# BreakoutBoard.net
KiCad netlist of a schematic drawn in EAGLE
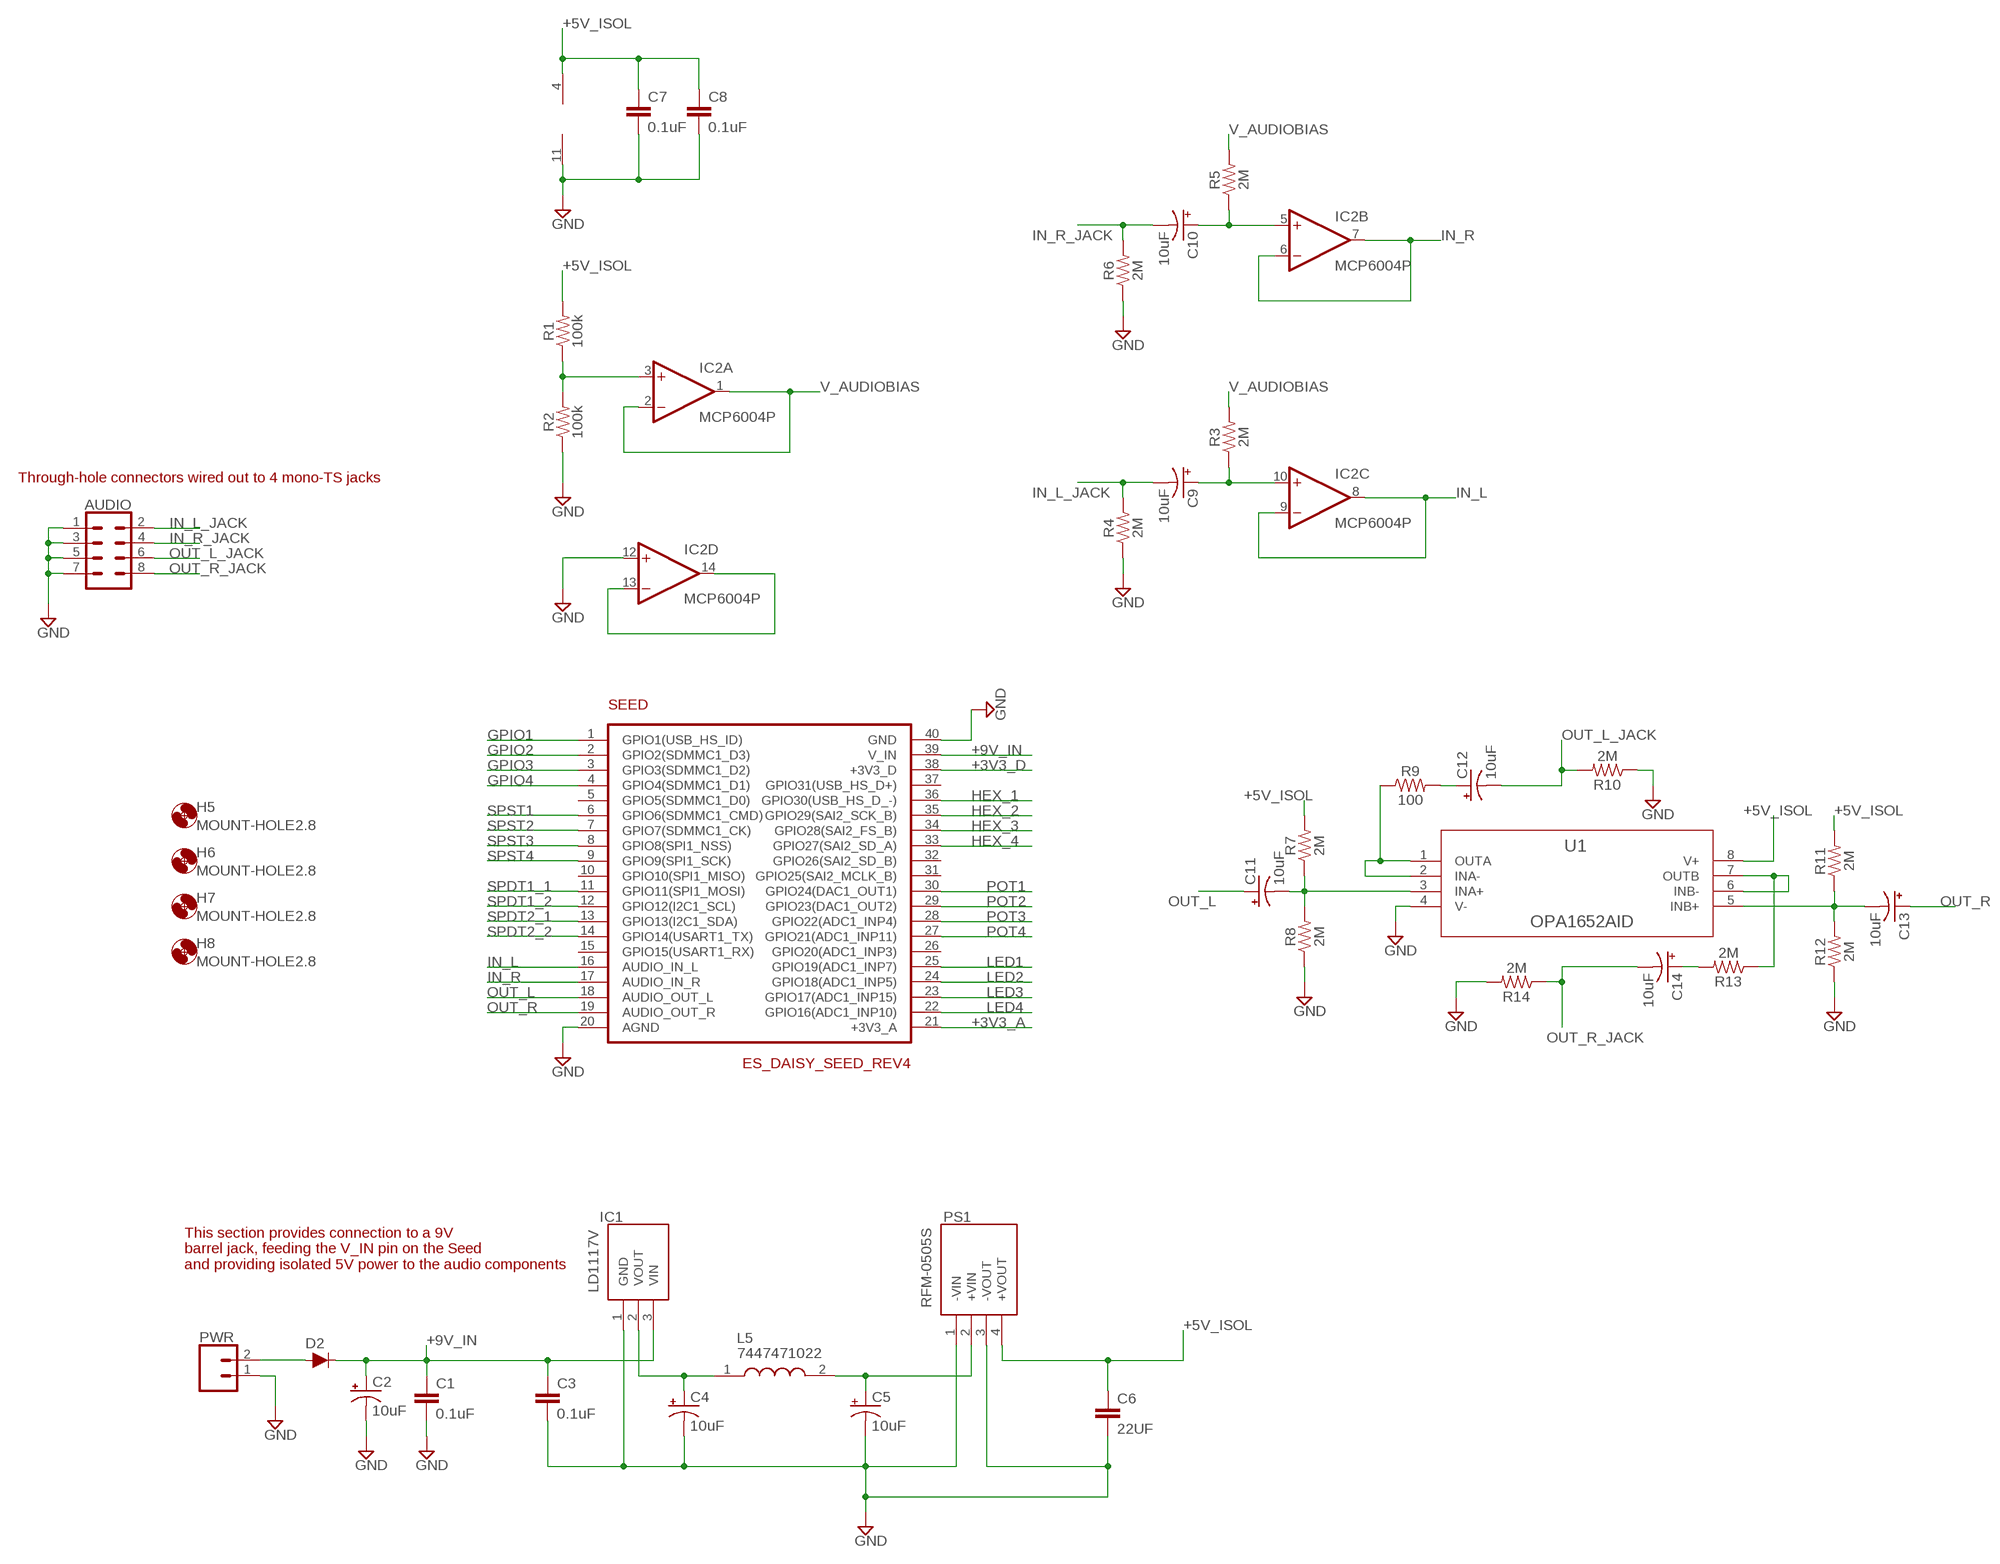
[diagram p0: schematic, sheet 1]
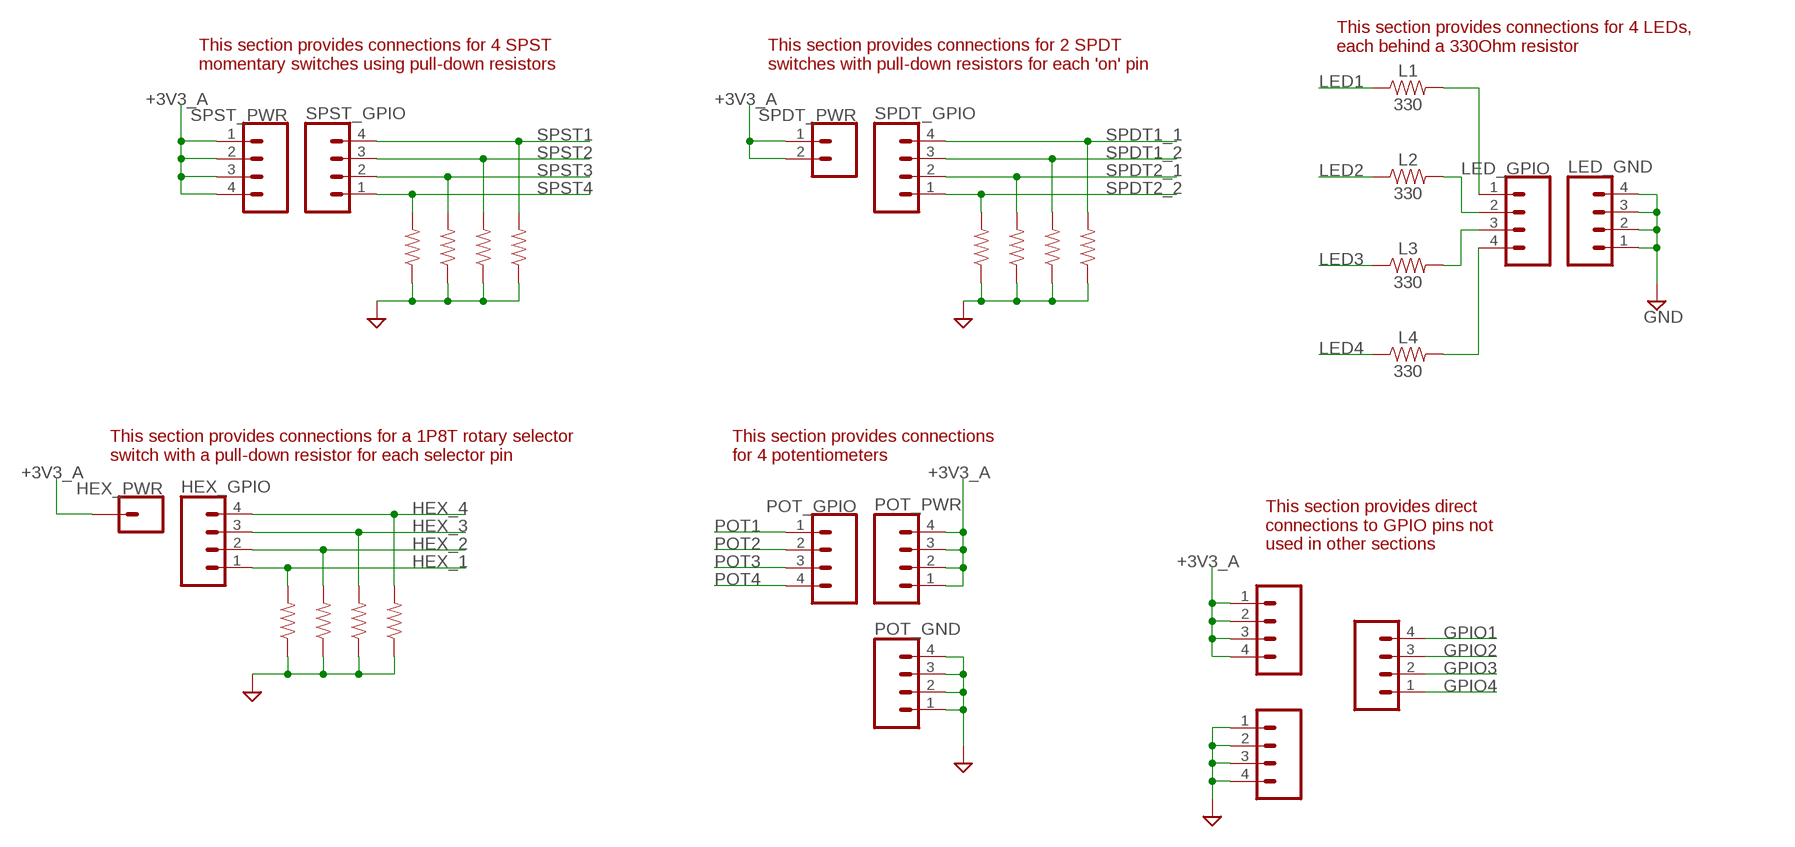
[diagram p1: schematic, sheet 2]

(export (version "E")
  (design (tool "Eeschema 10.0.6"))
  (components
    (comp (ref "AUDIO")
      (value "CONN_04X2")
      (footprint "eagle-import:2X4")
      (libsource (lib "eagle-import") (part "CONN_04X2"))
    )
    (comp (ref "C1")
      (value "0.1uF")
      (footprint "eagle-import:CAP-PTH-SMALL-KIT")
      (libsource (lib "eagle-import") (part "0.1UF-KIT-EZ-50V-20%"))
    )
    (comp (ref "C2")
      (value "10uF")
      (footprint "eagle-import:CPOL-RADIAL-2.5MM-5MM")
      (libsource (lib "eagle-import") (part "10UF-POLAR-RADIAL-2.5MM-25V-20%"))
    )
    (comp (ref "C3")
      (value "0.1uF")
      (footprint "eagle-import:CAP-PTH-SMALL-KIT")
      (libsource (lib "eagle-import") (part "0.1UF-KIT-EZ-50V-20%"))
    )
    (comp (ref "C4")
      (value "10uF")
      (footprint "eagle-import:CPOL-RADIAL-2.5MM-5MM")
      (libsource (lib "eagle-import") (part "10UF-POLAR-RADIAL-2.5MM-25V-20%"))
    )
    (comp (ref "C5")
      (value "10uF")
      (footprint "eagle-import:CPOL-RADIAL-2.5MM-5MM")
      (libsource (lib "eagle-import") (part "10UF-POLAR-RADIAL-2.5MM-25V-20%"))
    )
    (comp (ref "C6")
      (value "22UF")
      (footprint "eagle-import:CAP-PTH-SMALL-KIT")
      (libsource (lib "eagle-import") (part "22UF"))
    )
    (comp (ref "C7")
      (value "0.1uF")
      (footprint "eagle-import:CAP-PTH-SMALL-KIT")
      (libsource (lib "eagle-import") (part "0.1UF-KIT-EZ-50V-20%"))
    )
    (comp (ref "C8")
      (value "0.1uF")
      (footprint "eagle-import:CAP-PTH-SMALL-KIT")
      (libsource (lib "eagle-import") (part "0.1UF-KIT-EZ-50V-20%"))
    )
    (comp (ref "C9")
      (value "10uF")
      (footprint "eagle-import:CPOL-RADIAL-2.5MM-5MM")
      (libsource (lib "eagle-import") (part "10UF-POLAR-RADIAL-2.5MM-25V-20%"))
    )
    (comp (ref "C10")
      (value "10uF")
      (footprint "eagle-import:CPOL-RADIAL-2.5MM-5MM")
      (libsource (lib "eagle-import") (part "10UF-POLAR-RADIAL-2.5MM-25V-20%"))
    )
    (comp (ref "C11")
      (value "10uF")
      (footprint "eagle-import:CPOL-RADIAL-2.5MM-5MM")
      (libsource (lib "eagle-import") (part "10UF-POLAR-RADIAL-2.5MM-25V-20%"))
    )
    (comp (ref "C12")
      (value "10uF")
      (footprint "eagle-import:CPOL-RADIAL-2.5MM-5MM")
      (libsource (lib "eagle-import") (part "10UF-POLAR-RADIAL-2.5MM-25V-20%"))
    )
    (comp (ref "C13")
      (value "10uF")
      (footprint "eagle-import:CPOL-RADIAL-2.5MM-5MM")
      (libsource (lib "eagle-import") (part "10UF-POLAR-RADIAL-2.5MM-25V-20%"))
    )
    (comp (ref "C14")
      (value "10uF")
      (footprint "eagle-import:CPOL-RADIAL-2.5MM-5MM")
      (libsource (lib "eagle-import") (part "10UF-POLAR-RADIAL-2.5MM-25V-20%"))
    )
    (comp (ref "D2")
      (value "200mA/100V/1V")
      (footprint "eagle-import:DIODE-1N4148")
      (libsource (lib "eagle-import") (part "DIODE-1N4148"))
    )
    (comp (ref "H5")
      (value "MOUNT-HOLE2.8")
      (footprint "eagle-import:2,8")
      (libsource (lib "eagle-import") (part "MOUNT-HOLE2.8"))
    )
    (comp (ref "H6")
      (value "MOUNT-HOLE2.8")
      (footprint "eagle-import:2,8")
      (libsource (lib "eagle-import") (part "MOUNT-HOLE2.8"))
    )
    (comp (ref "H7")
      (value "MOUNT-HOLE2.8")
      (footprint "eagle-import:2,8")
      (libsource (lib "eagle-import") (part "MOUNT-HOLE2.8"))
    )
    (comp (ref "H8")
      (value "MOUNT-HOLE2.8")
      (footprint "eagle-import:2,8")
      (libsource (lib "eagle-import") (part "MOUNT-HOLE2.8"))
    )
    (comp (ref "IC1")
      (value "LD1117V")
      (footprint "eagle-import:TO255P460X1020X2008-3P")
      (fields (field (name "MOUSER_PART_NUMBER") "511-LD1117V"))
      (libsource (lib "eagle-import") (part "LD1117V"))
    )
    (comp (ref "IC2")
      (value "MCP6004P")
      (footprint "eagle-import:DIL14")
      (libsource (lib "eagle-import") (part "MCP6004P"))
    )
    (comp (ref "L5")
      (value "7447471022")
      (footprint "eagle-import:WE-TIS_111190")
      (fields (field (name "MOUSER_PART_NUMBER") "710-7447471022"))
      (libsource (lib "eagle-import") (part "7447471022"))
    )
    (comp (ref "PS1")
      (value "RFM-0505S")
      (footprint "eagle-import:RFM0505S")
      (fields (field (name "MOUSER_PART_NUMBER") "919-RFM-0505S"))
      (libsource (lib "eagle-import") (part "RFM-0505S"))
    )
    (comp (ref "PWR")
      (value "CONN_02")
      (footprint "eagle-import:1X02")
      (libsource (lib "eagle-import") (part "CONN_02"))
    )
    (comp (ref "R1")
      (value "100k")
      (footprint "eagle-import:AXIAL-0.3")
      (libsource (lib "eagle-import") (part "100KOHM-HORIZ-1/4W-5%"))
    )
    (comp (ref "R2")
      (value "100k")
      (footprint "eagle-import:AXIAL-0.3")
      (libsource (lib "eagle-import") (part "100KOHM-HORIZ-1/4W-5%"))
    )
    (comp (ref "R3")
      (value "2M")
      (footprint "eagle-import:AXIAL-0.3")
      (libsource (lib "eagle-import") (part "2MOHM-HORIZ-1/4W-5%"))
    )
    (comp (ref "R4")
      (value "2M")
      (footprint "eagle-import:AXIAL-0.3")
      (libsource (lib "eagle-import") (part "2MOHM-HORIZ-1/4W-5%"))
    )
    (comp (ref "R5")
      (value "2M")
      (footprint "eagle-import:AXIAL-0.3")
      (libsource (lib "eagle-import") (part "2MOHM-HORIZ-1/4W-5%"))
    )
    (comp (ref "R6")
      (value "2M")
      (footprint "eagle-import:AXIAL-0.3")
      (libsource (lib "eagle-import") (part "2MOHM-HORIZ-1/4W-5%"))
    )
    (comp (ref "R7")
      (value "2M")
      (footprint "eagle-import:AXIAL-0.3")
      (libsource (lib "eagle-import") (part "2MOHM-HORIZ-1/4W-5%"))
    )
    (comp (ref "R8")
      (value "2M")
      (footprint "eagle-import:AXIAL-0.3")
      (libsource (lib "eagle-import") (part "2MOHM-HORIZ-1/4W-5%"))
    )
    (comp (ref "R9")
      (value "100")
      (footprint "eagle-import:AXIAL-0.3")
      (libsource (lib "eagle-import") (part "100OHM-HORIZ-1/4W-1%"))
    )
    (comp (ref "R10")
      (value "2M")
      (footprint "eagle-import:AXIAL-0.3")
      (libsource (lib "eagle-import") (part "2MOHM-HORIZ-1/4W-5%"))
    )
    (comp (ref "R11")
      (value "2M")
      (footprint "eagle-import:AXIAL-0.3")
      (libsource (lib "eagle-import") (part "2MOHM-HORIZ-1/4W-5%"))
    )
    (comp (ref "R12")
      (value "2M")
      (footprint "eagle-import:AXIAL-0.3")
      (libsource (lib "eagle-import") (part "2MOHM-HORIZ-1/4W-5%"))
    )
    (comp (ref "R13")
      (value "2M")
      (footprint "eagle-import:AXIAL-0.3")
      (libsource (lib "eagle-import") (part "2MOHM-HORIZ-1/4W-5%"))
    )
    (comp (ref "R14")
      (value "2M")
      (footprint "eagle-import:AXIAL-0.3")
      (libsource (lib "eagle-import") (part "2MOHM-HORIZ-1/4W-5%"))
    )
    (comp (ref "SEED")
      (value "ES_DAISY_SEED_REV4")
      (footprint "eagle-import:ES_DAISY_SEED")
      (libsource (lib "eagle-import") (part "ES_DAISY_SEED_REV4"))
    )
    (comp (ref "U1")
      (value "OPA1652AID")
      (footprint "eagle-import:D8")
      (fields
        (field (name "GENERIC_PART_NUMBER") "OPA1652")
        (field (name "MANUFACTURER") "Texas Instruments")
      )
      (libsource (lib "eagle-import") (part "OPA1652AID"))
    )
    (comp (ref "D11")
      (value "10k")
      (footprint "eagle-import:AXIAL-0.3")
      (libsource (lib "eagle-import") (part "10KOHM-HORIZ-1/4W-5%"))
    )
    (comp (ref "D12")
      (value "10k")
      (footprint "eagle-import:AXIAL-0.3")
      (libsource (lib "eagle-import") (part "10KOHM-HORIZ-1/4W-5%"))
    )
    (comp (ref "D21")
      (value "10k")
      (footprint "eagle-import:AXIAL-0.3")
      (libsource (lib "eagle-import") (part "10KOHM-HORIZ-1/4W-5%"))
    )
    (comp (ref "D22")
      (value "10k")
      (footprint "eagle-import:AXIAL-0.3")
      (libsource (lib "eagle-import") (part "10KOHM-HORIZ-1/4W-5%"))
    )
    (comp (ref "EX_GND")
      (value "CONN_04")
      (footprint "eagle-import:1X04")
      (libsource (lib "eagle-import") (part "CONN_04"))
    )
    (comp (ref "EX_GPIOS")
      (value "CONN_04")
      (footprint "eagle-import:1X04")
      (libsource (lib "eagle-import") (part "CONN_04"))
    )
    (comp (ref "EX_PWR")
      (value "CONN_04")
      (footprint "eagle-import:1X04")
      (libsource (lib "eagle-import") (part "CONN_04"))
    )
    (comp (ref "H1")
      (value "10k")
      (footprint "eagle-import:AXIAL-0.3")
      (libsource (lib "eagle-import") (part "10KOHM-HORIZ-1/4W-5%"))
    )
    (comp (ref "H2")
      (value "10k")
      (footprint "eagle-import:AXIAL-0.3")
      (libsource (lib "eagle-import") (part "10KOHM-HORIZ-1/4W-5%"))
    )
    (comp (ref "H3")
      (value "10k")
      (footprint "eagle-import:AXIAL-0.3")
      (libsource (lib "eagle-import") (part "10KOHM-HORIZ-1/4W-5%"))
    )
    (comp (ref "H4")
      (value "10k")
      (footprint "eagle-import:AXIAL-0.3")
      (libsource (lib "eagle-import") (part "10KOHM-HORIZ-1/4W-5%"))
    )
    (comp (ref "HEX_GPIO")
      (value "CONN_04")
      (footprint "eagle-import:1X04")
      (libsource (lib "eagle-import") (part "CONN_04"))
    )
    (comp (ref "HEX_PWR")
      (value "CONN_01")
      (footprint "eagle-import:1X01")
      (libsource (lib "eagle-import") (part "CONN_01"))
    )
    (comp (ref "L1")
      (value "330")
      (footprint "eagle-import:AXIAL-0.3")
      (libsource (lib "eagle-import") (part "330OHM-HORIZ-1/10W-5%"))
    )
    (comp (ref "L2")
      (value "330")
      (footprint "eagle-import:AXIAL-0.3")
      (libsource (lib "eagle-import") (part "330OHM-HORIZ-1/10W-5%"))
    )
    (comp (ref "L3")
      (value "330")
      (footprint "eagle-import:AXIAL-0.3")
      (libsource (lib "eagle-import") (part "330OHM-HORIZ-1/10W-5%"))
    )
    (comp (ref "L4")
      (value "330")
      (footprint "eagle-import:AXIAL-0.3")
      (libsource (lib "eagle-import") (part "330OHM-HORIZ-1/10W-5%"))
    )
    (comp (ref "LED_GND")
      (value "CONN_04")
      (footprint "eagle-import:1X04")
      (libsource (lib "eagle-import") (part "CONN_04"))
    )
    (comp (ref "LED_GPIO")
      (value "CONN_04")
      (footprint "eagle-import:1X04")
      (libsource (lib "eagle-import") (part "CONN_04"))
    )
    (comp (ref "POT_GND")
      (value "CONN_04")
      (footprint "eagle-import:1X04")
      (libsource (lib "eagle-import") (part "CONN_04"))
    )
    (comp (ref "POT_GPIO")
      (value "CONN_04")
      (footprint "eagle-import:1X04")
      (libsource (lib "eagle-import") (part "CONN_04"))
    )
    (comp (ref "POT_PWR")
      (value "CONN_04")
      (footprint "eagle-import:1X04")
      (libsource (lib "eagle-import") (part "CONN_04"))
    )
    (comp (ref "S1")
      (value "10k")
      (footprint "eagle-import:AXIAL-0.3")
      (libsource (lib "eagle-import") (part "10KOHM-HORIZ-1/4W-5%"))
    )
    (comp (ref "S2")
      (value "10k")
      (footprint "eagle-import:AXIAL-0.3")
      (libsource (lib "eagle-import") (part "10KOHM-HORIZ-1/4W-5%"))
    )
    (comp (ref "S3")
      (value "10k")
      (footprint "eagle-import:AXIAL-0.3")
      (libsource (lib "eagle-import") (part "10KOHM-HORIZ-1/4W-5%"))
    )
    (comp (ref "S4")
      (value "10k")
      (footprint "eagle-import:AXIAL-0.3")
      (libsource (lib "eagle-import") (part "10KOHM-HORIZ-1/4W-5%"))
    )
    (comp (ref "SPDT_GPIO")
      (value "CONN_04")
      (footprint "eagle-import:1X04")
      (libsource (lib "eagle-import") (part "CONN_04"))
    )
    (comp (ref "SPDT_PWR")
      (value "CONN_02")
      (footprint "eagle-import:1X02")
      (libsource (lib "eagle-import") (part "CONN_02"))
    )
    (comp (ref "SPST_GPIO")
      (value "CONN_04")
      (footprint "eagle-import:1X04")
      (libsource (lib "eagle-import") (part "CONN_04"))
    )
    (comp (ref "SPST_PWR")
      (value "CONN_04")
      (footprint "eagle-import:1X04")
      (libsource (lib "eagle-import") (part "CONN_04"))
    )
  )
  (nets
    (net (code "1") (name "+3V3_A") (class "Default")
      (node (ref "EX_PWR") (pin "1") (pinfunction "1_1") (pintype "passive"))
      (node (ref "EX_PWR") (pin "2") (pinfunction "2_2") (pintype "passive"))
      (node (ref "EX_PWR") (pin "3") (pinfunction "3_3") (pintype "passive"))
      (node (ref "EX_PWR") (pin "4") (pinfunction "4_4") (pintype "passive"))
      (node (ref "HEX_PWR") (pin "1") (pinfunction "1_1") (pintype "passive"))
      (node (ref "POT_PWR") (pin "1") (pinfunction "1_1") (pintype "passive"))
      (node (ref "POT_PWR") (pin "2") (pinfunction "2_2") (pintype "passive"))
      (node (ref "POT_PWR") (pin "3") (pinfunction "3_3") (pintype "passive"))
      (node (ref "POT_PWR") (pin "4") (pinfunction "4_4") (pintype "passive"))
      (node (ref "SEED") (pin "21") (pinfunction "+3V3_A_21") (pintype "bidirectional"))
      (node (ref "SPDT_PWR") (pin "1") (pinfunction "1_1") (pintype "passive"))
      (node (ref "SPDT_PWR") (pin "2") (pinfunction "2_2") (pintype "passive"))
      (node (ref "SPST_PWR") (pin "1") (pinfunction "1_1") (pintype "passive"))
      (node (ref "SPST_PWR") (pin "2") (pinfunction "2_2") (pintype "passive"))
      (node (ref "SPST_PWR") (pin "3") (pinfunction "3_3") (pintype "passive"))
      (node (ref "SPST_PWR") (pin "4") (pinfunction "4_4") (pintype "passive"))
    )
    (net (code "2") (name "+3V3_D") (class "Default")
      (node (ref "SEED") (pin "38") (pinfunction "+3V3_D_38") (pintype "bidirectional"))
    )
    (net (code "3") (name "+5V_ISOL") (class "Default")
      (node (ref "C6") (pin "1") (pinfunction "1_1") (pintype "passive"))
      (node (ref "C7") (pin "1") (pinfunction "1_1") (pintype "passive"))
      (node (ref "C8") (pin "1") (pinfunction "1_1") (pintype "passive"))
      (node (ref "IC2") (pin "4") (pinfunction "V+_4") (pintype "power_in"))
      (node (ref "PS1") (pin "4") (pinfunction "+VOUT_4") (pintype "bidirectional"))
      (node (ref "R1") (pin "P$2") (pinfunction "2_P$2") (pintype "passive"))
      (node (ref "R11") (pin "P$2") (pinfunction "2_P$2") (pintype "passive"))
      (node (ref "R7") (pin "P$2") (pinfunction "2_P$2") (pintype "passive"))
      (node (ref "U1") (pin "8") (pinfunction "V+_8") (pintype "power_in"))
    )
    (net (code "4") (name "+9V_IN") (class "Default")
      (node (ref "C1") (pin "1") (pinfunction "1_1") (pintype "passive"))
      (node (ref "C2") (pin "1") (pinfunction "+_1") (pintype "passive"))
      (node (ref "C3") (pin "1") (pinfunction "1_1") (pintype "passive"))
      (node (ref "D2") (pin "C") (pinfunction "C_C") (pintype "passive"))
      (node (ref "IC1") (pin "3") (pinfunction "VIN_3") (pintype "bidirectional"))
      (node (ref "SEED") (pin "39") (pinfunction "V_IN_39") (pintype "bidirectional"))
    )
    (net (code "5") (name "GND") (class "Default")
      (node (ref "AUDIO") (pin "1") (pinfunction "1_1") (pintype "passive"))
      (node (ref "AUDIO") (pin "3") (pinfunction "3_3") (pintype "passive"))
      (node (ref "AUDIO") (pin "5") (pinfunction "5_5") (pintype "passive"))
      (node (ref "AUDIO") (pin "7") (pinfunction "7_7") (pintype "passive"))
      (node (ref "C1") (pin "2") (pinfunction "2_2") (pintype "passive"))
      (node (ref "C2") (pin "2") (pinfunction "-_2") (pintype "passive"))
      (node (ref "C3") (pin "2") (pinfunction "2_2") (pintype "passive"))
      (node (ref "C4") (pin "2") (pinfunction "-_2") (pintype "passive"))
      (node (ref "C5") (pin "2") (pinfunction "-_2") (pintype "passive"))
      (node (ref "C6") (pin "2") (pinfunction "2_2") (pintype "passive"))
      (node (ref "C7") (pin "2") (pinfunction "2_2") (pintype "passive"))
      (node (ref "C8") (pin "2") (pinfunction "2_2") (pintype "passive"))
      (node (ref "D11") (pin "P$1") (pinfunction "1_P$1") (pintype "passive"))
      (node (ref "D12") (pin "P$1") (pinfunction "1_P$1") (pintype "passive"))
      (node (ref "D21") (pin "P$1") (pinfunction "1_P$1") (pintype "passive"))
      (node (ref "D22") (pin "P$1") (pinfunction "1_P$1") (pintype "passive"))
      (node (ref "EX_GND") (pin "1") (pinfunction "1_1") (pintype "passive"))
      (node (ref "EX_GND") (pin "2") (pinfunction "2_2") (pintype "passive"))
      (node (ref "EX_GND") (pin "3") (pinfunction "3_3") (pintype "passive"))
      (node (ref "EX_GND") (pin "4") (pinfunction "4_4") (pintype "passive"))
      (node (ref "H1") (pin "P$1") (pinfunction "1_P$1") (pintype "passive"))
      (node (ref "H2") (pin "P$1") (pinfunction "1_P$1") (pintype "passive"))
      (node (ref "H3") (pin "P$1") (pinfunction "1_P$1") (pintype "passive"))
      (node (ref "H4") (pin "P$1") (pinfunction "1_P$1") (pintype "passive"))
      (node (ref "IC1") (pin "1") (pinfunction "GND_1") (pintype "bidirectional"))
      (node (ref "IC2") (pin "11") (pinfunction "V-_11") (pintype "power_in"))
      (node (ref "IC2") (pin "12") (pinfunction "+IN_12") (pintype "input"))
      (node (ref "LED_GND") (pin "1") (pinfunction "1_1") (pintype "passive"))
      (node (ref "LED_GND") (pin "2") (pinfunction "2_2") (pintype "passive"))
      (node (ref "LED_GND") (pin "3") (pinfunction "3_3") (pintype "passive"))
      (node (ref "LED_GND") (pin "4") (pinfunction "4_4") (pintype "passive"))
      (node (ref "POT_GND") (pin "1") (pinfunction "1_1") (pintype "passive"))
      (node (ref "POT_GND") (pin "2") (pinfunction "2_2") (pintype "passive"))
      (node (ref "POT_GND") (pin "3") (pinfunction "3_3") (pintype "passive"))
      (node (ref "POT_GND") (pin "4") (pinfunction "4_4") (pintype "passive"))
      (node (ref "PS1") (pin "1") (pinfunction "-VIN_1") (pintype "bidirectional"))
      (node (ref "PS1") (pin "3") (pinfunction "-VOUT_3") (pintype "bidirectional"))
      (node (ref "PWR") (pin "1") (pinfunction "1_1") (pintype "passive"))
      (node (ref "R10") (pin "P$1") (pinfunction "1_P$1") (pintype "passive"))
      (node (ref "R12") (pin "P$1") (pinfunction "1_P$1") (pintype "passive"))
      (node (ref "R14") (pin "P$2") (pinfunction "2_P$2") (pintype "passive"))
      (node (ref "R2") (pin "P$1") (pinfunction "1_P$1") (pintype "passive"))
      (node (ref "R4") (pin "P$1") (pinfunction "1_P$1") (pintype "passive"))
      (node (ref "R6") (pin "P$1") (pinfunction "1_P$1") (pintype "passive"))
      (node (ref "R8") (pin "P$1") (pinfunction "1_P$1") (pintype "passive"))
      (node (ref "S1") (pin "P$1") (pinfunction "1_P$1") (pintype "passive"))
      (node (ref "S2") (pin "P$1") (pinfunction "1_P$1") (pintype "passive"))
      (node (ref "S3") (pin "P$1") (pinfunction "1_P$1") (pintype "passive"))
      (node (ref "S4") (pin "P$1") (pinfunction "1_P$1") (pintype "passive"))
      (node (ref "SEED") (pin "20") (pinfunction "AGND_20") (pintype "bidirectional"))
      (node (ref "SEED") (pin "40") (pinfunction "GND_40") (pintype "bidirectional"))
      (node (ref "U1") (pin "4") (pinfunction "V-_4") (pintype "power_in"))
    )
    (net (code "6") (name "GPIO1") (class "Default")
      (node (ref "EX_GPIOS") (pin "4") (pinfunction "4_4") (pintype "passive"))
      (node (ref "SEED") (pin "1") (pinfunction "GPIO1(USB_HS_ID)_1") (pintype "bidirectional"))
    )
    (net (code "7") (name "GPIO2") (class "Default")
      (node (ref "EX_GPIOS") (pin "3") (pinfunction "3_3") (pintype "passive"))
      (node (ref "SEED") (pin "2") (pinfunction "GPIO2(SDMMC1_D3)_2") (pintype "bidirectional"))
    )
    (net (code "8") (name "GPIO3") (class "Default")
      (node (ref "EX_GPIOS") (pin "2") (pinfunction "2_2") (pintype "passive"))
      (node (ref "SEED") (pin "3") (pinfunction "GPIO3(SDMMC1_D2)_3") (pintype "bidirectional"))
    )
    (net (code "9") (name "GPIO4") (class "Default")
      (node (ref "EX_GPIOS") (pin "1") (pinfunction "1_1") (pintype "passive"))
      (node (ref "SEED") (pin "4") (pinfunction "GPIO4(SDMMC1_D1)_4") (pintype "bidirectional"))
    )
    (net (code "10") (name "HEX_1") (class "Default")
      (node (ref "H1") (pin "P$2") (pinfunction "2_P$2") (pintype "passive"))
      (node (ref "HEX_GPIO") (pin "1") (pinfunction "1_1") (pintype "passive"))
      (node (ref "SEED") (pin "36") (pinfunction "GPIO30(USB_HS_D_-)_36") (pintype "bidirectional"))
    )
    (net (code "11") (name "HEX_2") (class "Default")
      (node (ref "H2") (pin "P$2") (pinfunction "2_P$2") (pintype "passive"))
      (node (ref "HEX_GPIO") (pin "2") (pinfunction "2_2") (pintype "passive"))
      (node (ref "SEED") (pin "35") (pinfunction "GPIO29(SAI2_SCK_B)_35") (pintype "bidirectional"))
    )
    (net (code "12") (name "HEX_3") (class "Default")
      (node (ref "H3") (pin "P$2") (pinfunction "2_P$2") (pintype "passive"))
      (node (ref "HEX_GPIO") (pin "3") (pinfunction "3_3") (pintype "passive"))
      (node (ref "SEED") (pin "34") (pinfunction "GPIO28(SAI2_FS_B)_34") (pintype "bidirectional"))
    )
    (net (code "13") (name "HEX_4") (class "Default")
      (node (ref "H4") (pin "P$2") (pinfunction "2_P$2") (pintype "passive"))
      (node (ref "HEX_GPIO") (pin "4") (pinfunction "4_4") (pintype "passive"))
      (node (ref "SEED") (pin "33") (pinfunction "GPIO27(SAI2_SD_A)_33") (pintype "bidirectional"))
    )
    (net (code "14") (name "IN_L") (class "Default")
      (node (ref "IC2") (pin "8") (pinfunction "OUT_8") (pintype "output"))
      (node (ref "IC2") (pin "9") (pinfunction "-IN_9") (pintype "input"))
      (node (ref "SEED") (pin "16") (pinfunction "AUDIO_IN_L_16") (pintype "bidirectional"))
    )
    (net (code "15") (name "IN_L_JACK") (class "Default")
      (node (ref "AUDIO") (pin "2") (pinfunction "2_2") (pintype "passive"))
      (node (ref "C9") (pin "2") (pinfunction "-_2") (pintype "passive"))
      (node (ref "R4") (pin "P$2") (pinfunction "2_P$2") (pintype "passive"))
    )
    (net (code "16") (name "IN_R") (class "Default")
      (node (ref "IC2") (pin "6") (pinfunction "-IN_6") (pintype "input"))
      (node (ref "IC2") (pin "7") (pinfunction "OUT_7") (pintype "output"))
      (node (ref "SEED") (pin "17") (pinfunction "AUDIO_IN_R_17") (pintype "bidirectional"))
    )
    (net (code "17") (name "IN_R_JACK") (class "Default")
      (node (ref "AUDIO") (pin "4") (pinfunction "4_4") (pintype "passive"))
      (node (ref "C10") (pin "2") (pinfunction "-_2") (pintype "passive"))
      (node (ref "R6") (pin "P$2") (pinfunction "2_P$2") (pintype "passive"))
    )
    (net (code "18") (name "LED1") (class "Default")
      (node (ref "L1") (pin "P$1") (pinfunction "1_P$1") (pintype "passive"))
      (node (ref "SEED") (pin "25") (pinfunction "GPIO19(ADC1_INP7)_25") (pintype "bidirectional"))
    )
    (net (code "19") (name "LED2") (class "Default")
      (node (ref "L2") (pin "P$1") (pinfunction "1_P$1") (pintype "passive"))
      (node (ref "SEED") (pin "24") (pinfunction "GPIO18(ADC1_INP5)_24") (pintype "bidirectional"))
    )
    (net (code "20") (name "LED3") (class "Default")
      (node (ref "L3") (pin "P$1") (pinfunction "1_P$1") (pintype "passive"))
      (node (ref "SEED") (pin "23") (pinfunction "GPIO17(ADC1_INP15)_23") (pintype "bidirectional"))
    )
    (net (code "21") (name "LED4") (class "Default")
      (node (ref "L4") (pin "P$1") (pinfunction "1_P$1") (pintype "passive"))
      (node (ref "SEED") (pin "22") (pinfunction "GPIO16(ADC1_INP10)_22") (pintype "bidirectional"))
    )
    (net (code "22") (name "Net-(C4-+)") (class "Default")
      (node (ref "C4") (pin "1") (pinfunction "+_1") (pintype "passive"))
      (node (ref "IC1") (pin "2") (pinfunction "VOUT_2") (pintype "bidirectional"))
      (node (ref "L5") (pin "1") (pinfunction "1_1") (pintype "bidirectional"))
    )
    (net (code "23") (name "Net-(C5-+)") (class "Default")
      (node (ref "C5") (pin "1") (pinfunction "+_1") (pintype "passive"))
      (node (ref "L5") (pin "2") (pinfunction "2_2") (pintype "bidirectional"))
      (node (ref "PS1") (pin "2") (pinfunction "+VIN_2") (pintype "bidirectional"))
    )
    (net (code "24") (name "Net-(C9-+)") (class "Default")
      (node (ref "C9") (pin "1") (pinfunction "+_1") (pintype "passive"))
      (node (ref "IC2") (pin "10") (pinfunction "+IN_10") (pintype "input"))
      (node (ref "R3") (pin "P$1") (pinfunction "1_P$1") (pintype "passive"))
    )
    (net (code "25") (name "Net-(C10-+)") (class "Default")
      (node (ref "C10") (pin "1") (pinfunction "+_1") (pintype "passive"))
      (node (ref "IC2") (pin "5") (pinfunction "+IN_5") (pintype "input"))
      (node (ref "R5") (pin "P$1") (pinfunction "1_P$1") (pintype "passive"))
    )
    (net (code "26") (name "Net-(C11--)") (class "Default")
      (node (ref "C11") (pin "2") (pinfunction "-_2") (pintype "passive"))
      (node (ref "R7") (pin "P$1") (pinfunction "1_P$1") (pintype "passive"))
      (node (ref "R8") (pin "P$2") (pinfunction "2_P$2") (pintype "passive"))
      (node (ref "U1") (pin "3") (pinfunction "INA+_3") (pintype "input"))
    )
    (net (code "27") (name "Net-(C12-+)") (class "Default")
      (node (ref "C12") (pin "1") (pinfunction "+_1") (pintype "passive"))
      (node (ref "R9") (pin "P$2") (pinfunction "2_P$2") (pintype "passive"))
    )
    (net (code "28") (name "Net-(C13--)") (class "Default")
      (node (ref "C13") (pin "2") (pinfunction "-_2") (pintype "passive"))
      (node (ref "R11") (pin "P$1") (pinfunction "1_P$1") (pintype "passive"))
      (node (ref "R12") (pin "P$2") (pinfunction "2_P$2") (pintype "passive"))
      (node (ref "U1") (pin "5") (pinfunction "INB+_5") (pintype "input"))
    )
    (net (code "29") (name "Net-(C14-+)") (class "Default")
      (node (ref "C14") (pin "1") (pinfunction "+_1") (pintype "passive"))
      (node (ref "R13") (pin "P$2") (pinfunction "2_P$2") (pintype "passive"))
    )
    (net (code "30") (name "Net-(D2-PadA)") (class "Default")
      (node (ref "D2") (pin "A") (pinfunction "A_A") (pintype "passive"))
      (node (ref "PWR") (pin "2") (pinfunction "2_2") (pintype "passive"))
    )
    (net (code "31") (name "Net-(IC2A-+IN)") (class "Default")
      (node (ref "IC2") (pin "3") (pinfunction "+IN_3") (pintype "input"))
      (node (ref "R1") (pin "P$1") (pinfunction "1_P$1") (pintype "passive"))
      (node (ref "R2") (pin "P$2") (pinfunction "2_P$2") (pintype "passive"))
    )
    (net (code "32") (name "Net-(IC2D--IN)") (class "Default")
      (node (ref "IC2") (pin "13") (pinfunction "-IN_13") (pintype "input"))
      (node (ref "IC2") (pin "14") (pinfunction "OUT_14") (pintype "output"))
    )
    (net (code "33") (name "Net-(L1-2)") (class "Default")
      (node (ref "L1") (pin "P$2") (pinfunction "2_P$2") (pintype "passive"))
      (node (ref "LED_GPIO") (pin "1") (pinfunction "1_1") (pintype "passive"))
    )
    (net (code "34") (name "Net-(L2-2)") (class "Default")
      (node (ref "L2") (pin "P$2") (pinfunction "2_P$2") (pintype "passive"))
      (node (ref "LED_GPIO") (pin "2") (pinfunction "2_2") (pintype "passive"))
    )
    (net (code "35") (name "Net-(L3-2)") (class "Default")
      (node (ref "L3") (pin "P$2") (pinfunction "2_P$2") (pintype "passive"))
      (node (ref "LED_GPIO") (pin "3") (pinfunction "3_3") (pintype "passive"))
    )
    (net (code "36") (name "Net-(L4-2)") (class "Default")
      (node (ref "L4") (pin "P$2") (pinfunction "2_P$2") (pintype "passive"))
      (node (ref "LED_GPIO") (pin "4") (pinfunction "4_4") (pintype "passive"))
    )
    (net (code "37") (name "Net-(R9-1)") (class "Default")
      (node (ref "R9") (pin "P$1") (pinfunction "1_P$1") (pintype "passive"))
      (node (ref "U1") (pin "1") (pinfunction "OUTA_1") (pintype "output"))
      (node (ref "U1") (pin "2") (pinfunction "INA-_2") (pintype "input"))
    )
    (net (code "38") (name "Net-(R13-1)") (class "Default")
      (node (ref "R13") (pin "P$1") (pinfunction "1_P$1") (pintype "passive"))
      (node (ref "U1") (pin "6") (pinfunction "INB-_6") (pintype "input"))
      (node (ref "U1") (pin "7") (pinfunction "OUTB_7") (pintype "output"))
    )
    (net (code "39") (name "OUT_L") (class "Default")
      (node (ref "C11") (pin "1") (pinfunction "+_1") (pintype "passive"))
      (node (ref "SEED") (pin "18") (pinfunction "AUDIO_OUT_L_18") (pintype "bidirectional"))
    )
    (net (code "40") (name "OUT_L_JACK") (class "Default")
      (node (ref "AUDIO") (pin "6") (pinfunction "6_6") (pintype "passive"))
      (node (ref "C12") (pin "2") (pinfunction "-_2") (pintype "passive"))
      (node (ref "R10") (pin "P$2") (pinfunction "2_P$2") (pintype "passive"))
    )
    (net (code "41") (name "OUT_R") (class "Default")
      (node (ref "C13") (pin "1") (pinfunction "+_1") (pintype "passive"))
      (node (ref "SEED") (pin "19") (pinfunction "AUDIO_OUT_R_19") (pintype "bidirectional"))
    )
    (net (code "42") (name "OUT_R_JACK") (class "Default")
      (node (ref "AUDIO") (pin "8") (pinfunction "8_8") (pintype "passive"))
      (node (ref "C14") (pin "2") (pinfunction "-_2") (pintype "passive"))
      (node (ref "R14") (pin "P$1") (pinfunction "1_P$1") (pintype "passive"))
    )
    (net (code "43") (name "POT1") (class "Default")
      (node (ref "POT_GPIO") (pin "1") (pinfunction "1_1") (pintype "passive"))
      (node (ref "SEED") (pin "30") (pinfunction "GPIO24(DAC1_OUT1)_30") (pintype "bidirectional"))
    )
    (net (code "44") (name "POT2") (class "Default")
      (node (ref "POT_GPIO") (pin "2") (pinfunction "2_2") (pintype "passive"))
      (node (ref "SEED") (pin "29") (pinfunction "GPIO23(DAC1_OUT2)_29") (pintype "bidirectional"))
    )
    (net (code "45") (name "POT3") (class "Default")
      (node (ref "POT_GPIO") (pin "3") (pinfunction "3_3") (pintype "passive"))
      (node (ref "SEED") (pin "28") (pinfunction "GPIO22(ADC1_INP4)_28") (pintype "bidirectional"))
    )
    (net (code "46") (name "POT4") (class "Default")
      (node (ref "POT_GPIO") (pin "4") (pinfunction "4_4") (pintype "passive"))
      (node (ref "SEED") (pin "27") (pinfunction "GPIO21(ADC1_INP11)_27") (pintype "bidirectional"))
    )
    (net (code "47") (name "SPDT1_1") (class "Default")
      (node (ref "D11") (pin "P$2") (pinfunction "2_P$2") (pintype "passive"))
      (node (ref "SEED") (pin "11") (pinfunction "GPIO11(SPI1_MOSI)_11") (pintype "bidirectional"))
      (node (ref "SPDT_GPIO") (pin "4") (pinfunction "4_4") (pintype "passive"))
    )
    (net (code "48") (name "SPDT1_2") (class "Default")
      (node (ref "D12") (pin "P$2") (pinfunction "2_P$2") (pintype "passive"))
      (node (ref "SEED") (pin "12") (pinfunction "GPIO12(I2C1_SCL)_12") (pintype "bidirectional"))
      (node (ref "SPDT_GPIO") (pin "3") (pinfunction "3_3") (pintype "passive"))
    )
    (net (code "49") (name "SPDT2_1") (class "Default")
      (node (ref "D21") (pin "P$2") (pinfunction "2_P$2") (pintype "passive"))
      (node (ref "SEED") (pin "13") (pinfunction "GPIO13(I2C1_SDA)_13") (pintype "bidirectional"))
      (node (ref "SPDT_GPIO") (pin "2") (pinfunction "2_2") (pintype "passive"))
    )
    (net (code "50") (name "SPDT2_2") (class "Default")
      (node (ref "D22") (pin "P$2") (pinfunction "2_P$2") (pintype "passive"))
      (node (ref "SEED") (pin "14") (pinfunction "GPIO14(USART1_TX)_14") (pintype "bidirectional"))
      (node (ref "SPDT_GPIO") (pin "1") (pinfunction "1_1") (pintype "passive"))
    )
    (net (code "51") (name "SPST1") (class "Default")
      (node (ref "S1") (pin "P$2") (pinfunction "2_P$2") (pintype "passive"))
      (node (ref "SEED") (pin "6") (pinfunction "GPIO6(SDMMC1_CMD)_6") (pintype "bidirectional"))
      (node (ref "SPST_GPIO") (pin "4") (pinfunction "4_4") (pintype "passive"))
    )
    (net (code "52") (name "SPST2") (class "Default")
      (node (ref "S2") (pin "P$2") (pinfunction "2_P$2") (pintype "passive"))
      (node (ref "SEED") (pin "7") (pinfunction "GPIO7(SDMMC1_CK)_7") (pintype "bidirectional"))
      (node (ref "SPST_GPIO") (pin "3") (pinfunction "3_3") (pintype "passive"))
    )
    (net (code "53") (name "SPST3") (class "Default")
      (node (ref "S3") (pin "P$2") (pinfunction "2_P$2") (pintype "passive"))
      (node (ref "SEED") (pin "8") (pinfunction "GPIO8(SPI1_NSS)_8") (pintype "bidirectional"))
      (node (ref "SPST_GPIO") (pin "2") (pinfunction "2_2") (pintype "passive"))
    )
    (net (code "54") (name "SPST4") (class "Default")
      (node (ref "S4") (pin "P$2") (pinfunction "2_P$2") (pintype "passive"))
      (node (ref "SEED") (pin "9") (pinfunction "GPIO9(SPI1_SCK)_9") (pintype "bidirectional"))
      (node (ref "SPST_GPIO") (pin "1") (pinfunction "1_1") (pintype "passive"))
    )
    (net (code "55") (name "V_AUDIOBIAS") (class "Default")
      (node (ref "IC2") (pin "1") (pinfunction "OUT_1") (pintype "output"))
      (node (ref "IC2") (pin "2") (pinfunction "-IN_2") (pintype "input"))
      (node (ref "R3") (pin "P$2") (pinfunction "2_P$2") (pintype "passive"))
      (node (ref "R5") (pin "P$2") (pinfunction "2_P$2") (pintype "passive"))
    )
    (net (code "56") (name "unconnected-(SEED-GPIO5(SDMMC1_D0)-Pad5)") (class "Default")
      (node (ref "SEED") (pin "5") (pinfunction "GPIO5(SDMMC1_D0)_5") (pintype "bidirectional"))
    )
    (net (code "57") (name "unconnected-(SEED-GPIO10(SPI1_MISO)-Pad10)") (class "Default")
      (node (ref "SEED") (pin "10") (pinfunction "GPIO10(SPI1_MISO)_10") (pintype "bidirectional"))
    )
    (net (code "58") (name "unconnected-(SEED-GPIO15(USART1_RX)-Pad15)") (class "Default")
      (node (ref "SEED") (pin "15") (pinfunction "GPIO15(USART1_RX)_15") (pintype "bidirectional"))
    )
    (net (code "59") (name "unconnected-(SEED-GPIO20(ADC1_INP3)-Pad26)") (class "Default")
      (node (ref "SEED") (pin "26") (pinfunction "GPIO20(ADC1_INP3)_26") (pintype "bidirectional"))
    )
    (net (code "60") (name "unconnected-(SEED-GPIO25(SAI2_MCLK_B)-Pad31)") (class "Default")
      (node (ref "SEED") (pin "31") (pinfunction "GPIO25(SAI2_MCLK_B)_31") (pintype "bidirectional"))
    )
    (net (code "61") (name "unconnected-(SEED-GPIO26(SAI2_SD_B)-Pad32)") (class "Default")
      (node (ref "SEED") (pin "32") (pinfunction "GPIO26(SAI2_SD_B)_32") (pintype "bidirectional"))
    )
    (net (code "62") (name "unconnected-(SEED-GPIO31(USB_HS_D+)-Pad37)") (class "Default")
      (node (ref "SEED") (pin "37") (pinfunction "GPIO31(USB_HS_D+)_37") (pintype "bidirectional"))
    )
  )
)
